# TLV320DAC3100.net
KiCad netlist of a schematic drawn in Altium Designer
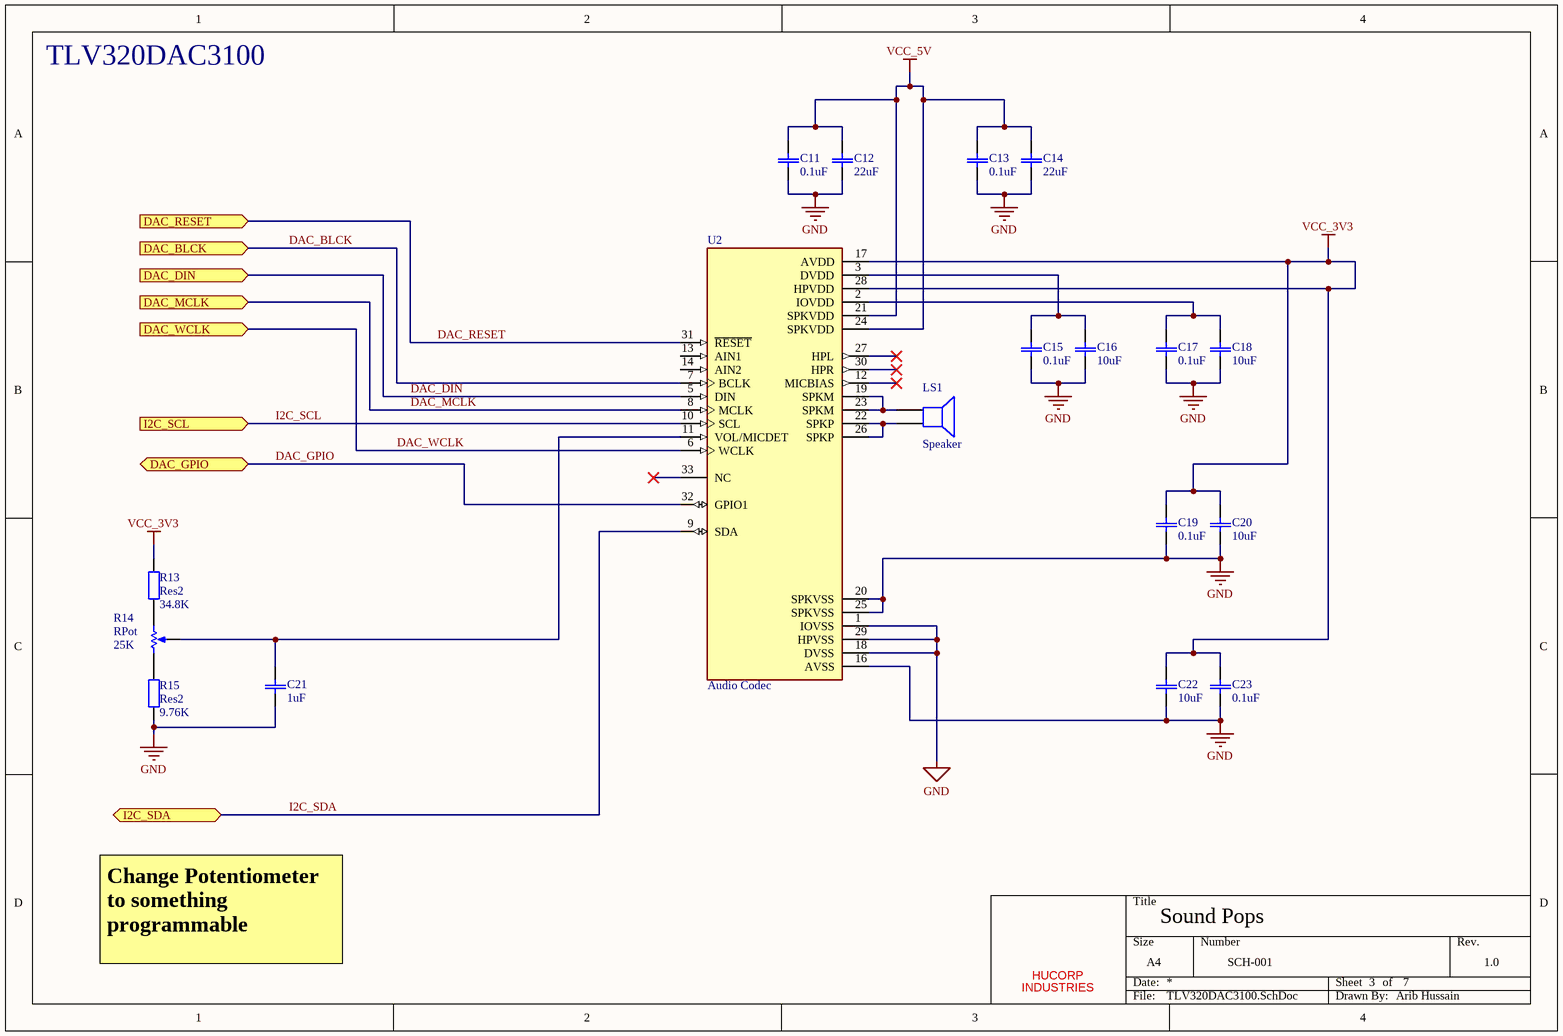
[diagram p0: TLV320DAC3100.SchDoc]

(export (version "E")
  (design (tool "Eeschema 10.0.6"))
  (components
    (comp (ref "C11")
      (value "0.1uF")
      (footprint "CAP_CL10_SAM")
      (description "CAP CER 0.1UF 25V X7R 0603")
      (fields
        (field (name "MANUFACTURER_PART_NUMBER") "CL10B104KA8NNNC")
        (field (name "Comment") "100 nF")
        (field (name "COPYRIGHT") "Copyright (C) 2022 Ultra Librarian. All rights reserved.")
      )
      (libsource (lib "Capacitors") (part "CL10B104KA8NNNC"))
    )
    (comp (ref "C12")
      (value "22uF")
      (footprint "CAP_CL10_SAM")
      (description "CAP CER 22UF 10V X5R 0603")
      (fields
        (field (name "MANUFACTURER_PART_NUMBER") "CL10A226MP8NUNE")
        (field (name "COPYRIGHT") "Copyright (C) 2023 Ultra Librarian. All rights reserved.")
      )
      (libsource (lib "Capacitors") (part "CL10A226MP8NUNE"))
    )
    (comp (ref "C13")
      (value "0.1uF")
      (footprint "CAP_CL10_SAM")
      (description "CAP CER 0.1UF 25V X7R 0603")
      (fields
        (field (name "MANUFACTURER_PART_NUMBER") "CL10B104KA8NNNC")
        (field (name "Comment") "100 nF")
        (field (name "COPYRIGHT") "Copyright (C) 2022 Ultra Librarian. All rights reserved.")
      )
      (libsource (lib "Capacitors") (part "CL10B104KA8NNNC"))
    )
    (comp (ref "C14")
      (value "22uF")
      (footprint "CAP_CL10_SAM")
      (description "CAP CER 22UF 10V X5R 0603")
      (fields
        (field (name "MANUFACTURER_PART_NUMBER") "CL10A226MP8NUNE")
        (field (name "COPYRIGHT") "Copyright (C) 2023 Ultra Librarian. All rights reserved.")
      )
      (libsource (lib "Capacitors") (part "CL10A226MP8NUNE"))
    )
    (comp (ref "C15")
      (value "0.1uF")
      (footprint "CAP_CL10_SAM")
      (description "CAP CER 0.1UF 25V X7R 0603")
      (fields
        (field (name "MANUFACTURER_PART_NUMBER") "CL10B104KA8NNNC")
        (field (name "Comment") "100 nF")
        (field (name "COPYRIGHT") "Copyright (C) 2022 Ultra Librarian. All rights reserved.")
      )
      (libsource (lib "Capacitors") (part "CL10B104KA8NNNC"))
    )
    (comp (ref "C16")
      (value "10uF")
      (footprint "CAP_CL10_SAM")
      (description "10 µF ±20% 6.3V Ceramic Capacitor X5R 0603 (1608 Metric)")
      (fields
        (field (name "MANUFACTURER_PART_NUMBER") "CL10A106MQ8NNNC")
        (field (name "Comment") "10 uF")
        (field (name "COPYRIGHT") "Copyright (C) 2022 Ultra Librarian. All rights reserved.")
      )
      (libsource (lib "Capacitors") (part "CL10A106MQ8NNNC"))
    )
    (comp (ref "C17")
      (value "0.1uF")
      (footprint "CAP_CL10_SAM")
      (description "CAP CER 0.1UF 25V X7R 0603")
      (fields
        (field (name "MANUFACTURER_PART_NUMBER") "CL10B104KA8NNNC")
        (field (name "Comment") "100 nF")
        (field (name "COPYRIGHT") "Copyright (C) 2022 Ultra Librarian. All rights reserved.")
      )
      (libsource (lib "Capacitors") (part "CL10B104KA8NNNC"))
    )
    (comp (ref "C18")
      (value "10uF")
      (footprint "CAP_CL10_SAM")
      (description "10 µF ±20% 6.3V Ceramic Capacitor X5R 0603 (1608 Metric)")
      (fields
        (field (name "MANUFACTURER_PART_NUMBER") "CL10A106MQ8NNNC")
        (field (name "Comment") "10 uF")
        (field (name "COPYRIGHT") "Copyright (C) 2022 Ultra Librarian. All rights reserved.")
      )
      (libsource (lib "Capacitors") (part "CL10A106MQ8NNNC"))
    )
    (comp (ref "C19")
      (value "0.1uF")
      (footprint "CAP_CL10_SAM")
      (description "CAP CER 0.1UF 25V X7R 0603")
      (fields
        (field (name "MANUFACTURER_PART_NUMBER") "CL10B104KA8NNNC")
        (field (name "Comment") "100 nF")
        (field (name "COPYRIGHT") "Copyright (C) 2022 Ultra Librarian. All rights reserved.")
      )
      (libsource (lib "Capacitors") (part "CL10B104KA8NNNC"))
    )
    (comp (ref "C20")
      (value "10uF")
      (footprint "CAP_CL10_SAM")
      (description "10 µF ±20% 6.3V Ceramic Capacitor X5R 0603 (1608 Metric)")
      (fields
        (field (name "MANUFACTURER_PART_NUMBER") "CL10A106MQ8NNNC")
        (field (name "Comment") "10 uF")
        (field (name "COPYRIGHT") "Copyright (C) 2022 Ultra Librarian. All rights reserved.")
      )
      (libsource (lib "Capacitors") (part "CL10A106MQ8NNNC"))
    )
    (comp (ref "C21")
      (value "1uF")
      (footprint "CAP_CL10_SAM")
      (description "CAP CER 1UF 25V X5R 0603")
      (fields
        (field (name "MANUFACTURER_PART_NUMBER") "CL10B104KA8NNNC")
        (field (name "COPYRIGHT") "Copyright (C) 2022 Ultra Librarian. All rights reserved.")
      )
      (libsource (lib "Capacitors") (part "CL10A105KA8NNNC"))
    )
    (comp (ref "C22")
      (value "10uF")
      (footprint "CAP_CL10_SAM")
      (description "10 µF ±20% 6.3V Ceramic Capacitor X5R 0603 (1608 Metric)")
      (fields
        (field (name "MANUFACTURER_PART_NUMBER") "CL10A106MQ8NNNC")
        (field (name "Comment") "10 uF")
        (field (name "COPYRIGHT") "Copyright (C) 2022 Ultra Librarian. All rights reserved.")
      )
      (libsource (lib "Capacitors") (part "CL10A106MQ8NNNC"))
    )
    (comp (ref "C23")
      (value "0.1uF")
      (footprint "CAP_CL10_SAM")
      (description "CAP CER 0.1UF 25V X7R 0603")
      (fields
        (field (name "MANUFACTURER_PART_NUMBER") "CL10B104KA8NNNC")
        (field (name "Comment") "100 nF")
        (field (name "COPYRIGHT") "Copyright (C) 2022 Ultra Librarian. All rights reserved.")
      )
      (libsource (lib "Capacitors") (part "CL10B104KA8NNNC"))
    )
    (comp (ref "LS1")
      (value "Speaker")
      (footprint "PIN2")
      (description "Loudspeaker")
      (fields (field (name "PUBLISHER") "Altium Limited"))
      (libsource (lib "Miscellaneous Devices") (part "Speaker"))
    )
    (comp (ref "R13")
      (value "Res2")
      (footprint "AXIAL-0.4")
      (description "Resistor")
      (fields (field (name "ALTIUM_VALUE") "34.8K") (field (name "PUBLISHER") "Altium Limited"))
      (libsource (lib "Miscellaneous Devices") (part "Res2"))
    )
    (comp (ref "R14")
      (value "RPot")
      (footprint "VR5")
      (description "Potentiometer")
      (fields (field (name "ALTIUM_VALUE") "25K") (field (name "PUBLISHER") "Altium Limited"))
      (libsource (lib "Miscellaneous Devices") (part "RPot"))
    )
    (comp (ref "R15")
      (value "Res2")
      (footprint "AXIAL-0.4")
      (description "Resistor")
      (fields (field (name "ALTIUM_VALUE") "9.76K") (field (name "PUBLISHER") "Altium Limited"))
      (libsource (lib "Miscellaneous Devices") (part "Res2"))
    )
    (comp (ref "U2")
      (value "Audio Codec")
      (footprint "IC_ADS125H01IRHBT:IC_ADS125H01IRHBT")
      (description "Low-Power Stereo Audio DAC With Mono Class-D Speaker Amplifier 32-VQFN -40 to 85")
      (fields (field (name "DIGI-KEY_PART_NUMBER") "296-39266-1-ND") (field (name "MF") "Texas Instruments"))
      (libsource (lib "AUDIO") (part "TLV320DAC3100IRHBT"))
    )
  )
  (nets
    (net (code "1") (name "/DAC_BLCK") (class "Default")
      (node (ref "U2") (pin "7") (pinfunction "BCLK_7") (pintype "input"))
    )
    (net (code "2") (name "/DAC_DIN") (class "Default")
      (node (ref "U2") (pin "5") (pinfunction "DIN_5") (pintype "input"))
    )
    (net (code "3") (name "/DAC_GPIO") (class "Default")
      (node (ref "U2") (pin "32") (pinfunction "GPIO1_32") (pintype "bidirectional"))
    )
    (net (code "4") (name "/DAC_MCLK") (class "Default")
      (node (ref "U2") (pin "8") (pinfunction "MCLK_8") (pintype "input"))
    )
    (net (code "5") (name "/DAC_RESET") (class "Default")
      (node (ref "U2") (pin "31") (pinfunction "~{RESET}_31") (pintype "input"))
    )
    (net (code "6") (name "/DAC_WCLK") (class "Default")
      (node (ref "U2") (pin "6") (pinfunction "WCLK_6") (pintype "input"))
    )
    (net (code "7") (name "/I2C_SCL") (class "Default")
      (node (ref "U2") (pin "10") (pinfunction "SCL_10") (pintype "input"))
    )
    (net (code "8") (name "/I2C_SDA") (class "Default")
      (node (ref "U2") (pin "9") (pinfunction "SDA_9") (pintype "bidirectional"))
    )
    (net (code "9") (name "GND") (class "Default")
      (node (ref "C11") (pin "1") (pinfunction "1_1") (pintype "passive"))
      (node (ref "C12") (pin "1") (pinfunction "1_1") (pintype "passive"))
      (node (ref "C13") (pin "1") (pinfunction "1_1") (pintype "passive"))
      (node (ref "C14") (pin "1") (pinfunction "1_1") (pintype "passive"))
      (node (ref "C15") (pin "1") (pinfunction "1_1") (pintype "passive"))
      (node (ref "C16") (pin "1") (pinfunction "1_1") (pintype "passive"))
      (node (ref "C17") (pin "1") (pinfunction "1_1") (pintype "passive"))
      (node (ref "C18") (pin "1") (pinfunction "1_1") (pintype "passive"))
      (node (ref "C19") (pin "1") (pinfunction "1_1") (pintype "passive"))
      (node (ref "C20") (pin "1") (pinfunction "1_1") (pintype "passive"))
      (node (ref "C21") (pin "1") (pinfunction "1_1") (pintype "passive"))
      (node (ref "C22") (pin "1") (pinfunction "1_1") (pintype "passive"))
      (node (ref "C23") (pin "1") (pinfunction "1_1") (pintype "passive"))
      (node (ref "R15") (pin "1") (pinfunction "1_1") (pintype "passive"))
      (node (ref "U2") (pin "1") (pinfunction "IOVSS_1") (pintype "power_in"))
      (node (ref "U2") (pin "16") (pinfunction "AVSS_16") (pintype "power_in"))
      (node (ref "U2") (pin "18") (pinfunction "DVSS_18") (pintype "power_in"))
      (node (ref "U2") (pin "20") (pinfunction "SPKVSS_20") (pintype "power_in"))
      (node (ref "U2") (pin "25") (pinfunction "SPKVSS_25") (pintype "power_in"))
      (node (ref "U2") (pin "29") (pinfunction "HPVSS_29") (pintype "power_in"))
    )
    (net (code "10") (name "Net-(LS1-Pad1)") (class "Default")
      (node (ref "LS1") (pin "1") (pinfunction "1_1") (pintype "passive"))
      (node (ref "U2") (pin "19") (pinfunction "SPKM_19") (pintype "passive"))
      (node (ref "U2") (pin "23") (pinfunction "SPKM_23") (pintype "passive"))
    )
    (net (code "11") (name "Net-(LS1-Pad2)") (class "Default")
      (node (ref "LS1") (pin "2") (pinfunction "2_2") (pintype "passive"))
      (node (ref "U2") (pin "22") (pinfunction "SPKP_22") (pintype "passive"))
      (node (ref "U2") (pin "26") (pinfunction "SPKP_26") (pintype "passive"))
    )
    (net (code "12") (name "Net-(R14-BOT)") (class "Default")
      (node (ref "R13") (pin "1") (pinfunction "1_1") (pintype "passive"))
      (node (ref "R14") (pin "2") (pinfunction "BOT_2") (pintype "passive"))
    )
    (net (code "13") (name "Net-(R14-TAP)") (class "Default")
      (node (ref "C21") (pin "2") (pinfunction "2_2") (pintype "passive"))
      (node (ref "R14") (pin "3") (pinfunction "TAP_3") (pintype "passive"))
      (node (ref "U2") (pin "11") (pinfunction "VOL/MICDET_11") (pintype "input"))
    )
    (net (code "14") (name "Net-(R14-TOP)") (class "Default")
      (node (ref "R14") (pin "1") (pinfunction "TOP_1") (pintype "passive"))
      (node (ref "R15") (pin "2") (pinfunction "2_2") (pintype "passive"))
    )
    (net (code "15") (name "Net-(U2-DVDD)") (class "Default")
      (node (ref "C15") (pin "2") (pinfunction "2_2") (pintype "passive"))
      (node (ref "C16") (pin "2") (pinfunction "2_2") (pintype "passive"))
      (node (ref "U2") (pin "3") (pinfunction "DVDD_3") (pintype "passive"))
    )
    (net (code "16") (name "Net-(U2-IOVDD)") (class "Default")
      (node (ref "C17") (pin "2") (pinfunction "2_2") (pintype "passive"))
      (node (ref "C18") (pin "2") (pinfunction "2_2") (pintype "passive"))
      (node (ref "U2") (pin "2") (pinfunction "IOVDD_2") (pintype "passive"))
    )
    (net (code "17") (name "VCC_3V3") (class "Default")
      (node (ref "C19") (pin "2") (pinfunction "2_2") (pintype "passive"))
      (node (ref "C20") (pin "2") (pinfunction "2_2") (pintype "passive"))
      (node (ref "C22") (pin "2") (pinfunction "2_2") (pintype "passive"))
      (node (ref "C23") (pin "2") (pinfunction "2_2") (pintype "passive"))
      (node (ref "R13") (pin "2") (pinfunction "2_2") (pintype "passive"))
      (node (ref "U2") (pin "17") (pinfunction "AVDD_17") (pintype "passive"))
      (node (ref "U2") (pin "28") (pinfunction "HPVDD_28") (pintype "passive"))
    )
    (net (code "18") (name "VCC_5V") (class "Default")
      (node (ref "C11") (pin "2") (pinfunction "2_2") (pintype "passive"))
      (node (ref "C12") (pin "2") (pinfunction "2_2") (pintype "passive"))
      (node (ref "C13") (pin "2") (pinfunction "2_2") (pintype "passive"))
      (node (ref "C14") (pin "2") (pinfunction "2_2") (pintype "passive"))
      (node (ref "U2") (pin "21") (pinfunction "SPKVDD_21") (pintype "passive"))
      (node (ref "U2") (pin "24") (pinfunction "SPKVDD_24") (pintype "passive"))
    )
    (net (code "19") (name "unconnected-(U2-AIN1-Pad13)") (class "Default")
      (node (ref "U2") (pin "13") (pinfunction "AIN1_13") (pintype "input"))
    )
    (net (code "20") (name "unconnected-(U2-AIN2-Pad14)") (class "Default")
      (node (ref "U2") (pin "14") (pinfunction "AIN2_14") (pintype "input"))
    )
    (net (code "21") (name "unconnected-(U2-HPL-Pad27)") (class "Default")
      (node (ref "U2") (pin "27") (pinfunction "HPL_27") (pintype "output+no_connect"))
    )
    (net (code "22") (name "unconnected-(U2-HPR-Pad30)") (class "Default")
      (node (ref "U2") (pin "30") (pinfunction "HPR_30") (pintype "output+no_connect"))
    )
    (net (code "23") (name "unconnected-(U2-MICBIAS-Pad12)") (class "Default")
      (node (ref "U2") (pin "12") (pinfunction "MICBIAS_12") (pintype "output+no_connect"))
    )
    (net (code "24") (name "unconnected-(U2-NC-Pad33)") (class "Default")
      (node (ref "U2") (pin "33") (pinfunction "NC_33") (pintype "passive+no_connect"))
    )
  )
)
